# io_expansion.net
KiCad netlist of a schematic drawn in Altium Designer
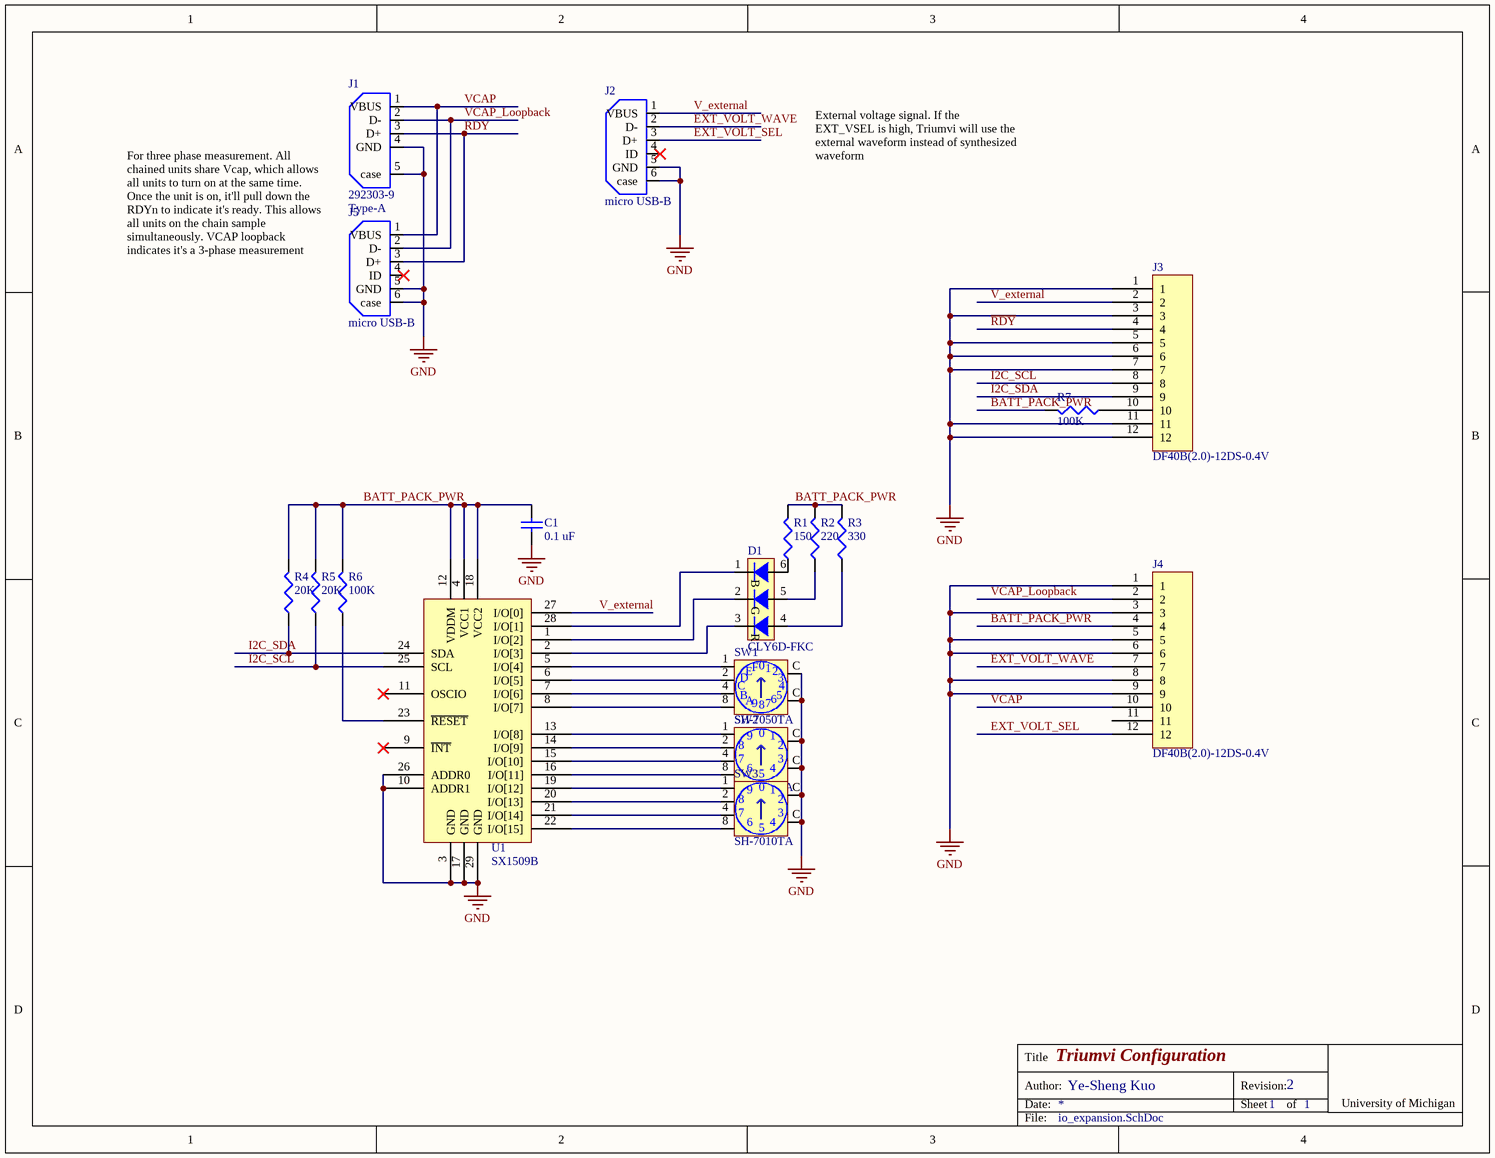
[diagram p0: io_expansion.SchDoc]

(export (version "E")
  (design (tool "Eeschema 10.0.6"))
  (components
    (comp (ref "C1")
      (value "0.1 uF")
      (footprint "0603")
      (description "Ceramic capacitor, 0.1 uF, 0603 package")
      (fields (field (name "TOLERANCE") "10%") (field (name "Comment") "Ceramic capacitor"))
      (libsource (lib "rlc") (part "C_0.1u_25V_0603_ceramic"))
    )
    (comp (ref "D1")
      (value "CLY6D-FKC")
      (footprint "PLCC6")
      (description "CREE PLCC6 3 in 1 SMD LED")
      (libsource (lib "rlc") (part "D_CLY6D-FKC"))
    )
    (comp (ref "J1")
      (value "292303-9")
      (footprint "292303-9")
      (description "USB 2.0 Type A")
      (fields (field (name "TYPE") "Type-A"))
      (libsource (lib "connectors") (part "292303-9"))
    )
    (comp (ref "J2")
      (value "micro USB-B")
      (footprint "Micro USB-B")
      (description "CONN USB MICRO B RECPT SMT R/A")
      (libsource (lib "connectors") (part "Micro USB"))
    )
    (comp (ref "J3")
      (value "DF40B(2.0)-12DS-0.4V")
      (footprint "DF40B(2.0)-12DS-0.4V")
      (description "Hirose BM20 Series, 0.4mm pitch, 2mm stack height, 12 pos, header")
      (libsource (lib "connectors") (part "DF40B(2.0)-12DS-0.4V"))
    )
    (comp (ref "J4")
      (value "DF40B(2.0)-12DS-0.4V")
      (footprint "DF40B(2.0)-12DS-0.4V")
      (description "Hirose BM20 Series, 0.4mm pitch, 2mm stack height, 12 pos, header")
      (libsource (lib "connectors") (part "DF40B(2.0)-12DS-0.4V"))
    )
    (comp (ref "J5")
      (value "micro USB-B")
      (footprint "Micro USB-B")
      (description "CONN USB MICRO B RECPT SMT R/A")
      (libsource (lib "connectors") (part "Micro USB"))
    )
    (comp (ref "R1")
      (value "150")
      (footprint "0603")
      (description "Chip resistor, 150,  0603 package")
      (fields (field (name "TOLERANCE") "1%") (field (name "POWER") "1/1 W"))
      (libsource (lib "rlc") (part "R_150_0603"))
    )
    (comp (ref "R2")
      (value "220")
      (footprint "0603")
      (description "Chip resistor, 220, 0603 package")
      (fields (field (name "TOLERANCE") "1%") (field (name "POWER") "1/10 W"))
      (libsource (lib "rlc") (part "R_220_0603"))
    )
    (comp (ref "R3")
      (value "330")
      (footprint "0603")
      (description "Chip resistor, 330, 0603 package")
      (fields (field (name "TOLERANCE") "1%") (field (name "POWER") "1/10 W"))
      (libsource (lib "rlc") (part "R_330_0603"))
    )
    (comp (ref "R4")
      (value "20K")
      (footprint "0603")
      (description "Chip resistor, 20K, 0603 package")
      (fields (field (name "TOLERANCE") "1%") (field (name "POWER") "1/10 W"))
      (libsource (lib "rlc") (part "R_20K_0603"))
    )
    (comp (ref "R5")
      (value "20K")
      (footprint "0603")
      (description "Chip resistor, 20K, 0603 package")
      (fields (field (name "TOLERANCE") "1%") (field (name "POWER") "1/10 W"))
      (libsource (lib "rlc") (part "R_20K_0603"))
    )
    (comp (ref "R6")
      (value "100K")
      (footprint "0603")
      (description "Chip resistor, 100K, 0603 package")
      (fields (field (name "TOLERANCE") "1%") (field (name "POWER") "1/10 W"))
      (libsource (lib "rlc") (part "R_100K_0603"))
    )
    (comp (ref "R7")
      (value "100K")
      (footprint "0603")
      (description "Chip resistor, 100K, 0603 package")
      (fields (field (name "TOLERANCE") "1%") (field (name "POWER") "1/10 W"))
      (libsource (lib "rlc") (part "R_100K_0603"))
    )
    (comp (ref "SW1")
      (value "SH-7050TA")
      (footprint "SH-7050A")
      (description "ROTARY CODED SWITCHES")
      (libsource (lib "switches") (part "SH-7050TA"))
    )
    (comp (ref "SW2")
      (value "SH-7010TA")
      (footprint "SH-7010A")
      (description "ROTARY CODED SWITCHES")
      (libsource (lib "switches") (part "SH-7010TA"))
    )
    (comp (ref "SW3")
      (value "SH-7010TA")
      (footprint "SH-7010A")
      (description "ROTARY CODED SWITCHES")
      (libsource (lib "switches") (part "SH-7010TA"))
    )
    (comp (ref "U1")
      (value "SX1509B")
      (footprint "QFN40P400X400X60_HS-29N")
      (description "Voltage Level Shifting GPIO  with LED Driver and Keypad Engine")
      (libsource (lib "io_expansion") (part "SX1509B"))
    )
  )
  (nets
    (net (code "1") (name "/BATT_PACK_PWR") (class "Default")
      (node (ref "C1") (pin "1") (pintype "passive"))
      (node (ref "J4") (pin "4") (pinfunction "4_4") (pintype "passive"))
      (node (ref "R1") (pin "1") (pintype "passive"))
      (node (ref "R2") (pin "1") (pintype "passive"))
      (node (ref "R3") (pin "1") (pintype "passive"))
      (node (ref "R4") (pin "1") (pintype "passive"))
      (node (ref "R5") (pin "1") (pintype "passive"))
      (node (ref "R6") (pin "1") (pintype "passive"))
      (node (ref "R7") (pin "1") (pintype "passive"))
      (node (ref "U1") (pin "12") (pinfunction "VDDM_12") (pintype "passive"))
      (node (ref "U1") (pin "18") (pinfunction "VCC2_18") (pintype "passive"))
      (node (ref "U1") (pin "4") (pinfunction "VCC1_4") (pintype "passive"))
    )
    (net (code "2") (name "/EXT_VOLT_SEL") (class "Default")
      (node (ref "J2") (pin "3") (pinfunction "D+_3") (pintype "power_in"))
      (node (ref "J4") (pin "12") (pinfunction "12_12") (pintype "passive"))
    )
    (net (code "3") (name "/EXT_VOLT_WAVE") (class "Default")
      (node (ref "J2") (pin "2") (pinfunction "D-_2") (pintype "power_in"))
      (node (ref "J4") (pin "7") (pinfunction "7_7") (pintype "passive"))
    )
    (net (code "4") (name "/I2C_SCL") (class "Default")
      (node (ref "J3") (pin "8") (pinfunction "8_8") (pintype "passive"))
      (node (ref "R5") (pin "2") (pintype "passive"))
      (node (ref "U1") (pin "25") (pinfunction "SCL_25") (pintype "passive"))
    )
    (net (code "5") (name "/I2C_SDA") (class "Default")
      (node (ref "J3") (pin "9") (pinfunction "9_9") (pintype "passive"))
      (node (ref "R4") (pin "2") (pintype "passive"))
      (node (ref "U1") (pin "24") (pinfunction "SDA_24") (pintype "passive"))
    )
    (net (code "6") (name "/VCAP") (class "Default")
      (node (ref "J1") (pin "1") (pinfunction "VBUS_1") (pintype "power_in"))
      (node (ref "J4") (pin "10") (pinfunction "10_10") (pintype "passive"))
      (node (ref "J5") (pin "1") (pinfunction "VBUS_1") (pintype "power_in"))
    )
    (net (code "7") (name "/VCAP_Loopback") (class "Default")
      (node (ref "J1") (pin "2") (pinfunction "D-_2") (pintype "power_in"))
      (node (ref "J4") (pin "2") (pinfunction "2_2") (pintype "passive"))
      (node (ref "J5") (pin "2") (pinfunction "D-_2") (pintype "power_in"))
    )
    (net (code "8") (name "/V_external") (class "Default")
      (node (ref "J2") (pin "1") (pinfunction "VBUS_1") (pintype "power_in"))
      (node (ref "J3") (pin "2") (pinfunction "2_2") (pintype "passive"))
      (node (ref "U1") (pin "27") (pinfunction "I/O[0]_27") (pintype "passive"))
    )
    (net (code "9") (name "/~{RDY}") (class "Default")
      (node (ref "J1") (pin "3") (pinfunction "D+_3") (pintype "power_in"))
      (node (ref "J3") (pin "4") (pinfunction "4_4") (pintype "passive"))
      (node (ref "J5") (pin "3") (pinfunction "D+_3") (pintype "power_in"))
    )
    (net (code "10") (name "GND") (class "Default")
      (node (ref "C1") (pin "2") (pintype "passive"))
      (node (ref "J1") (pin "4") (pinfunction "GND_4") (pintype "power_in"))
      (node (ref "J1") (pin "5") (pinfunction "case_5") (pintype "power_in"))
      (node (ref "J2") (pin "5") (pinfunction "GND_5") (pintype "power_in"))
      (node (ref "J2") (pin "6") (pinfunction "case_6") (pintype "power_in"))
      (node (ref "J3") (pin "1") (pinfunction "1_1") (pintype "passive"))
      (node (ref "J3") (pin "11") (pinfunction "11_11") (pintype "passive"))
      (node (ref "J3") (pin "12") (pinfunction "12_12") (pintype "passive"))
      (node (ref "J3") (pin "3") (pinfunction "3_3") (pintype "passive"))
      (node (ref "J3") (pin "5") (pinfunction "5_5") (pintype "passive"))
      (node (ref "J3") (pin "6") (pinfunction "6_6") (pintype "passive"))
      (node (ref "J3") (pin "7") (pinfunction "7_7") (pintype "passive"))
      (node (ref "J4") (pin "1") (pinfunction "1_1") (pintype "passive"))
      (node (ref "J4") (pin "3") (pinfunction "3_3") (pintype "passive"))
      (node (ref "J4") (pin "5") (pinfunction "5_5") (pintype "passive"))
      (node (ref "J4") (pin "6") (pinfunction "6_6") (pintype "passive"))
      (node (ref "J4") (pin "8") (pinfunction "8_8") (pintype "passive"))
      (node (ref "J4") (pin "9") (pinfunction "9_9") (pintype "passive"))
      (node (ref "J5") (pin "5") (pinfunction "GND_5") (pintype "power_in"))
      (node (ref "J5") (pin "6") (pinfunction "case_6") (pintype "power_in"))
      (node (ref "SW1") (pin "C") (pinfunction "C_C") (pintype "passive"))
      (node (ref "SW2") (pin "C") (pinfunction "C_C") (pintype "passive"))
      (node (ref "SW3") (pin "C") (pinfunction "C_C") (pintype "passive"))
      (node (ref "U1") (pin "10") (pinfunction "ADDR1_10") (pintype "passive"))
      (node (ref "U1") (pin "17") (pinfunction "GND_17") (pintype "passive"))
      (node (ref "U1") (pin "26") (pinfunction "ADDR0_26") (pintype "passive"))
      (node (ref "U1") (pin "29") (pinfunction "GND_29") (pintype "passive"))
      (node (ref "U1") (pin "3") (pinfunction "GND_3") (pintype "passive"))
    )
    (net (code "11") (name "Net-(D1-Pad4)") (class "Default")
      (node (ref "D1") (pin "4") (pinfunction "4_4") (pintype "passive"))
      (node (ref "R3") (pin "2") (pintype "passive"))
    )
    (net (code "12") (name "Net-(D1-Pad5)") (class "Default")
      (node (ref "D1") (pin "5") (pinfunction "5_5") (pintype "passive"))
      (node (ref "R2") (pin "2") (pintype "passive"))
    )
    (net (code "13") (name "Net-(D1-Pad6)") (class "Default")
      (node (ref "D1") (pin "6") (pinfunction "6_6") (pintype "passive"))
      (node (ref "R1") (pin "2") (pintype "passive"))
    )
    (net (code "14") (name "Net-(J3-Pad10)") (class "Default")
      (node (ref "J3") (pin "10") (pinfunction "10_10") (pintype "passive"))
      (node (ref "R7") (pin "2") (pintype "passive"))
    )
    (net (code "15") (name "Net-(U1-I{slash}O[1])") (class "Default")
      (node (ref "D1") (pin "1") (pintype "passive"))
      (node (ref "U1") (pin "28") (pinfunction "I/O[1]_28") (pintype "passive"))
    )
    (net (code "16") (name "Net-(U1-I{slash}O[2])") (class "Default")
      (node (ref "D1") (pin "2") (pintype "passive"))
      (node (ref "U1") (pin "1") (pinfunction "I/O[2]_1") (pintype "passive"))
    )
    (net (code "17") (name "Net-(U1-I{slash}O[3])") (class "Default")
      (node (ref "D1") (pin "3") (pinfunction "3_3") (pintype "passive"))
      (node (ref "U1") (pin "2") (pinfunction "I/O[3]_2") (pintype "passive"))
    )
    (net (code "18") (name "Net-(U1-I{slash}O[4])") (class "Default")
      (node (ref "SW1") (pin "1") (pinfunction "1_1") (pintype "passive"))
      (node (ref "U1") (pin "5") (pinfunction "I/O[4]_5") (pintype "passive"))
    )
    (net (code "19") (name "Net-(U1-I{slash}O[5])") (class "Default")
      (node (ref "SW1") (pin "2") (pinfunction "2_2") (pintype "passive"))
      (node (ref "U1") (pin "6") (pinfunction "I/O[5]_6") (pintype "passive"))
    )
    (net (code "20") (name "Net-(U1-I{slash}O[6])") (class "Default")
      (node (ref "SW1") (pin "4") (pinfunction "4_4") (pintype "passive"))
      (node (ref "U1") (pin "7") (pinfunction "I/O[6]_7") (pintype "passive"))
    )
    (net (code "21") (name "Net-(U1-I{slash}O[7])") (class "Default")
      (node (ref "SW1") (pin "8") (pinfunction "8_8") (pintype "passive"))
      (node (ref "U1") (pin "8") (pinfunction "I/O[7]_8") (pintype "passive"))
    )
    (net (code "22") (name "Net-(U1-I{slash}O[8])") (class "Default")
      (node (ref "SW2") (pin "1") (pinfunction "1_1") (pintype "passive"))
      (node (ref "U1") (pin "13") (pinfunction "I/O[8]_13") (pintype "passive"))
    )
    (net (code "23") (name "Net-(U1-I{slash}O[9])") (class "Default")
      (node (ref "SW2") (pin "2") (pinfunction "2_2") (pintype "passive"))
      (node (ref "U1") (pin "14") (pinfunction "I/O[9]_14") (pintype "passive"))
    )
    (net (code "24") (name "Net-(U1-I{slash}O[10])") (class "Default")
      (node (ref "SW2") (pin "4") (pinfunction "4_4") (pintype "passive"))
      (node (ref "U1") (pin "15") (pinfunction "I/O[10]_15") (pintype "passive"))
    )
    (net (code "25") (name "Net-(U1-I{slash}O[11])") (class "Default")
      (node (ref "SW2") (pin "8") (pinfunction "8_8") (pintype "passive"))
      (node (ref "U1") (pin "16") (pinfunction "I/O[11]_16") (pintype "passive"))
    )
    (net (code "26") (name "Net-(U1-I{slash}O[12])") (class "Default")
      (node (ref "SW3") (pin "1") (pinfunction "1_1") (pintype "passive"))
      (node (ref "U1") (pin "19") (pinfunction "I/O[12]_19") (pintype "passive"))
    )
    (net (code "27") (name "Net-(U1-I{slash}O[13])") (class "Default")
      (node (ref "SW3") (pin "2") (pinfunction "2_2") (pintype "passive"))
      (node (ref "U1") (pin "20") (pinfunction "I/O[13]_20") (pintype "passive"))
    )
    (net (code "28") (name "Net-(U1-I{slash}O[14])") (class "Default")
      (node (ref "SW3") (pin "4") (pinfunction "4_4") (pintype "passive"))
      (node (ref "U1") (pin "21") (pinfunction "I/O[14]_21") (pintype "passive"))
    )
    (net (code "29") (name "Net-(U1-I{slash}O[15])") (class "Default")
      (node (ref "SW3") (pin "8") (pinfunction "8_8") (pintype "passive"))
      (node (ref "U1") (pin "22") (pinfunction "I/O[15]_22") (pintype "passive"))
    )
    (net (code "30") (name "Net-(U1-~{RESET})") (class "Default")
      (node (ref "R6") (pin "2") (pintype "passive"))
      (node (ref "U1") (pin "23") (pinfunction "~{RESET}_23") (pintype "passive"))
    )
    (net (code "31") (name "unconnected-(J2-ID-Pad4)") (class "Default")
      (node (ref "J2") (pin "4") (pinfunction "ID_4") (pintype "power_in+no_connect"))
    )
    (net (code "32") (name "unconnected-(J4-Pad11)") (class "Default")
      (node (ref "J4") (pin "11") (pinfunction "11_11") (pintype "passive"))
    )
    (net (code "33") (name "unconnected-(J5-ID-Pad4)") (class "Default")
      (node (ref "J5") (pin "4") (pinfunction "ID_4") (pintype "power_in+no_connect"))
    )
    (net (code "34") (name "unconnected-(U1-OSCIO-Pad11)") (class "Default")
      (node (ref "U1") (pin "11") (pinfunction "OSCIO_11") (pintype "passive+no_connect"))
    )
    (net (code "35") (name "unconnected-(U1-~{INT}-Pad9)") (class "Default")
      (node (ref "U1") (pin "9") (pinfunction "~{INT}_9") (pintype "passive+no_connect"))
    )
  )
)
